# Qwiic_GPS-RTK2_-_ublox_ZED-F9P.net
KiCad netlist of a schematic drawn in EAGLE
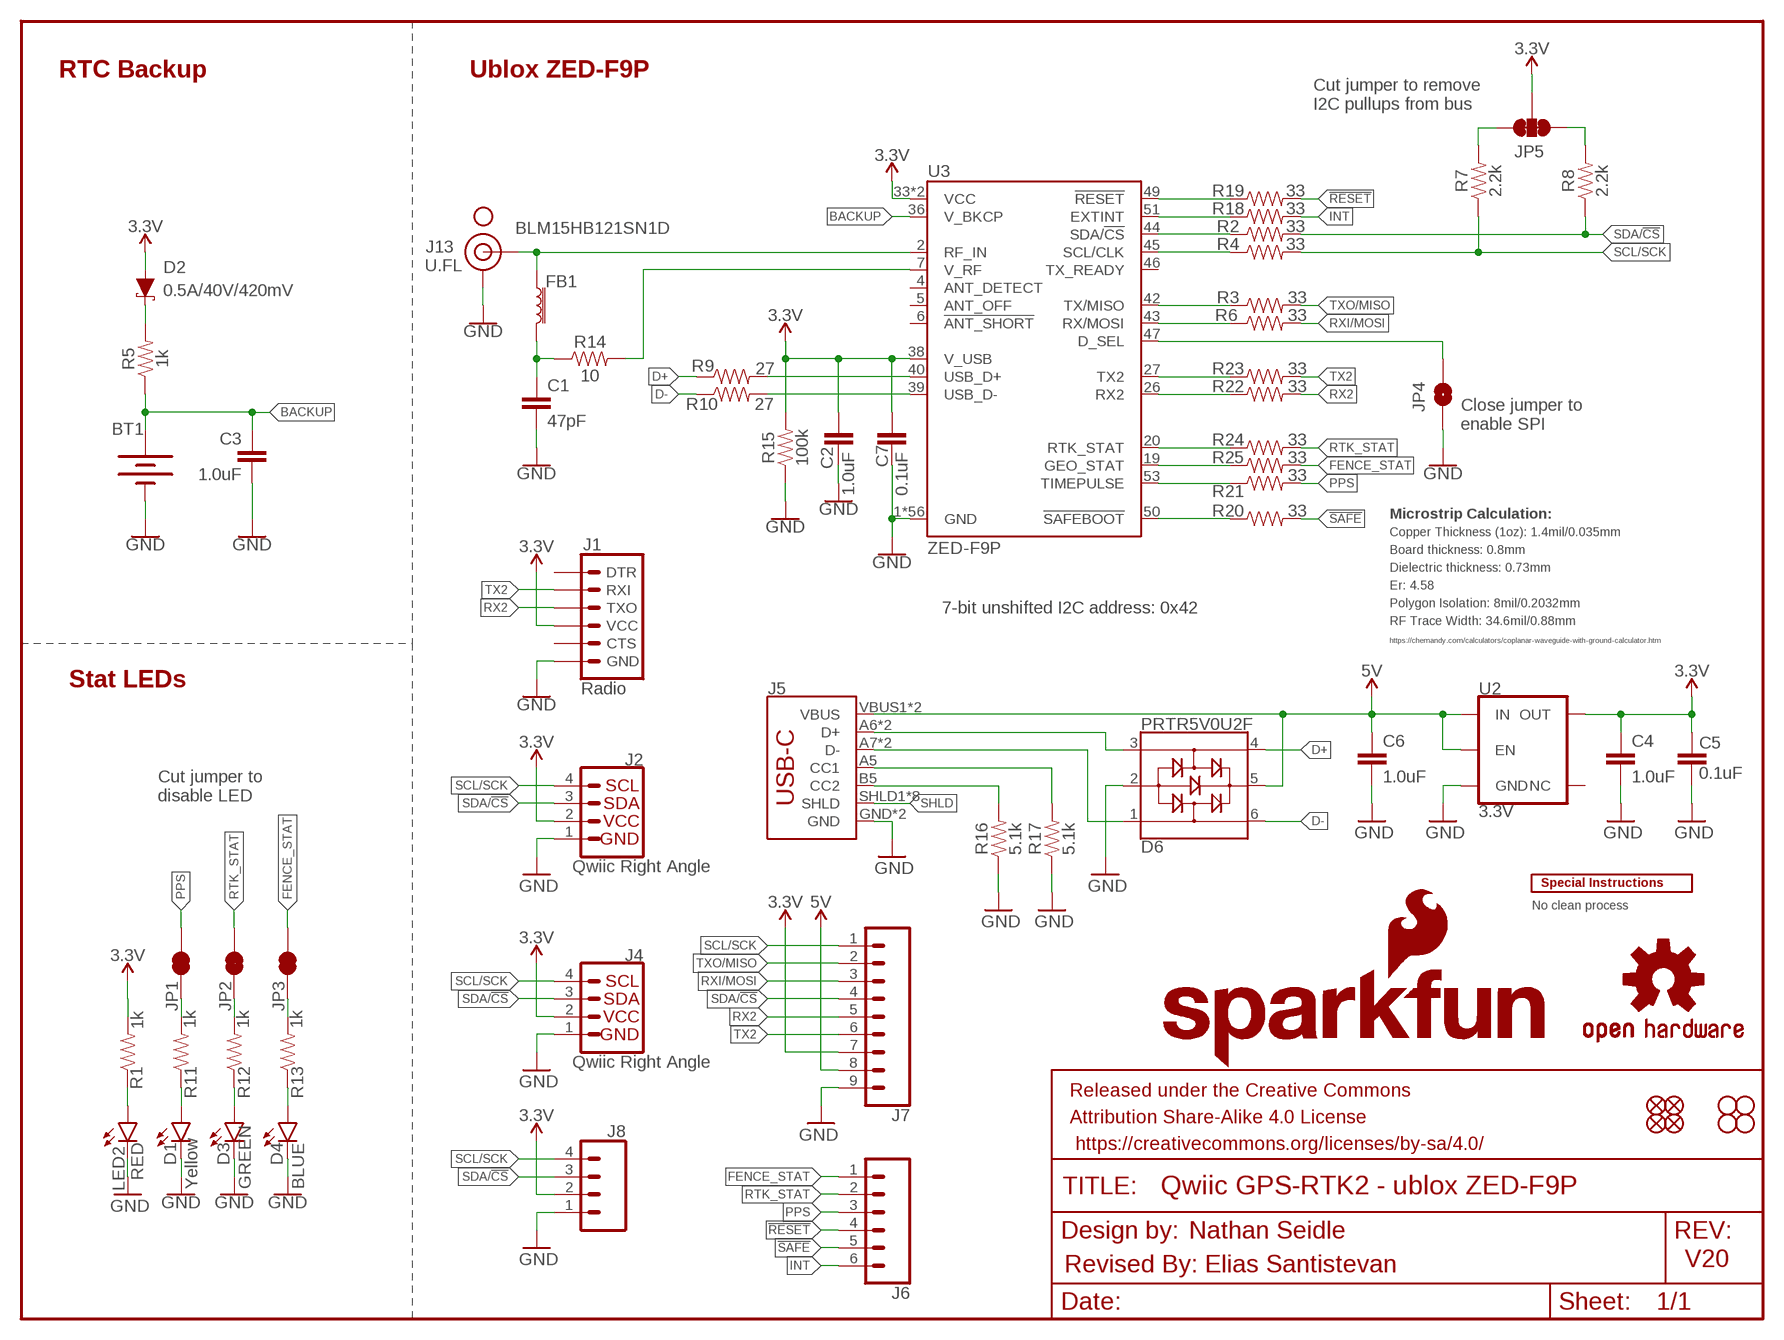
[diagram p0: schematic, sheet 1]

(export (version "E")
  (design (tool "Eeschema 10.0.6"))
  (components
    (comp (ref "BT1")
      (value "ML414H_IV01E_BATTERY")
      (footprint "eagle-import:ML414H_IV01E")
      (libsource (lib "eagle-import") (part "ML414H_IV01E_BATTERY"))
    )
    (comp (ref "C1")
      (value "47pF")
      (footprint "eagle-import:0603")
      (libsource (lib "eagle-import") (part "47PF-0603-50V-5%"))
    )
    (comp (ref "C2")
      (value "1.0uF")
      (footprint "eagle-import:0603")
      (libsource (lib "eagle-import") (part "1.0UF-0603-16V-10%"))
    )
    (comp (ref "C3")
      (value "1.0uF")
      (footprint "eagle-import:0603")
      (libsource (lib "eagle-import") (part "1.0UF-0603-16V-10%"))
    )
    (comp (ref "C4")
      (value "1.0uF")
      (footprint "eagle-import:0603")
      (libsource (lib "eagle-import") (part "1.0UF-0603-16V-10%"))
    )
    (comp (ref "C5")
      (value "0.1uF")
      (footprint "eagle-import:0603")
      (libsource (lib "eagle-import") (part "0.1UF-0603-25V-(+80/-20%)"))
    )
    (comp (ref "C6")
      (value "1.0uF")
      (footprint "eagle-import:0603")
      (libsource (lib "eagle-import") (part "1.0UF-0603-16V-10%"))
    )
    (comp (ref "C7")
      (value "0.1uF")
      (footprint "eagle-import:0603")
      (libsource (lib "eagle-import") (part "0.1UF-0603-25V-(+80/-20%)"))
    )
    (comp (ref "D1")
      (value "Yellow")
      (footprint "eagle-import:LED-0603")
      (libsource (lib "eagle-import") (part "LED-YELLOW0603"))
    )
    (comp (ref "D2")
      (value "0.5A/40V/420mV")
      (footprint "eagle-import:SOD-323")
      (libsource (lib "eagle-import") (part "DIODE-SCHOTTKY-PMEG4005EJ"))
    )
    (comp (ref "D3")
      (value "GREEN")
      (footprint "eagle-import:LED-0603")
      (libsource (lib "eagle-import") (part "LED-GREEN0603"))
    )
    (comp (ref "D4")
      (value "BLUE")
      (footprint "eagle-import:LED-0603")
      (libsource (lib "eagle-import") (part "LED-BLUE0603"))
    )
    (comp (ref "D6")
      (value "PRTR5V0U2F")
      (footprint "eagle-import:SOT886")
      (libsource (lib "eagle-import") (part "PRTR5V0U2F"))
    )
    (comp (ref "FB1")
      (value "FERRITE_BEAD-120_OHM-0402")
      (footprint "eagle-import:0402")
      (fields (field (name "MFG_PART") "BLM15HB121SN1D"))
      (libsource (lib "eagle-import") (part "FERRITE_BEAD-120_OHM-0402"))
    )
    (comp (ref "FRAME1")
      (value "FRAME-LETTER")
      (footprint "eagle-import:CREATIVE_COMMONS")
      (libsource (lib "eagle-import") (part "FRAME-LETTER"))
    )
    (comp (ref "J1")
      (value "Radio")
      (footprint "eagle-import:1X06_NO_SILK")
      (libsource (lib "eagle-import") (part "6_PIN_SERIAL_TARGET_NO_SILK"))
    )
    (comp (ref "J2")
      (value "Qwiic Right Angle")
      (footprint "eagle-import:JST04_1MM_RA")
      (libsource (lib "eagle-import") (part "I2C_STANDARDQWIIC"))
    )
    (comp (ref "J4")
      (value "Qwiic Right Angle")
      (footprint "eagle-import:JST04_1MM_RA")
      (libsource (lib "eagle-import") (part "I2C_STANDARDQWIIC"))
    )
    (comp (ref "J5")
      (value "USB_C2-LAYER")
      (footprint "eagle-import:USB-C-16P")
      (libsource (lib "eagle-import") (part "USB_C2-LAYER"))
    )
    (comp (ref "J6")
      (value "CONN_06NO_SILK_FEMALE_PTH")
      (footprint "eagle-import:1X06_NO_SILK")
      (libsource (lib "eagle-import") (part "CONN_06NO_SILK_FEMALE_PTH"))
    )
    (comp (ref "J7")
      (value "CONN_09NO_SILK")
      (footprint "eagle-import:1X09_NO_SILK")
      (libsource (lib "eagle-import") (part "CONN_09NO_SILK"))
    )
    (comp (ref "J8")
      (value "CONN_041X04_NO_SILK")
      (footprint "eagle-import:1X04_NO_SILK")
      (libsource (lib "eagle-import") (part "CONN_041X04_NO_SILK"))
    )
    (comp (ref "J13")
      (value "U.FL")
      (footprint "eagle-import:U.FL")
      (libsource (lib "eagle-import") (part "U.FL2PIN"))
    )
    (comp (ref "JP1")
      (value "JUMPER-SMT_2_NC_TRACE_SILK")
      (footprint "eagle-import:SMT-JUMPER_2_NC_TRACE_SILK")
      (libsource (lib "eagle-import") (part "JUMPER-SMT_2_NC_TRACE_SILK"))
    )
    (comp (ref "JP2")
      (value "JUMPER-SMT_2_NC_TRACE_SILK")
      (footprint "eagle-import:SMT-JUMPER_2_NC_TRACE_SILK")
      (libsource (lib "eagle-import") (part "JUMPER-SMT_2_NC_TRACE_SILK"))
    )
    (comp (ref "JP3")
      (value "JUMPER-SMT_2_NC_TRACE_SILK")
      (footprint "eagle-import:SMT-JUMPER_2_NC_TRACE_SILK")
      (libsource (lib "eagle-import") (part "JUMPER-SMT_2_NC_TRACE_SILK"))
    )
    (comp (ref "JP4")
      (value "JUMPER-SMT_2_NO_SILK")
      (footprint "eagle-import:SMT-JUMPER_2_NO_SILK")
      (libsource (lib "eagle-import") (part "JUMPER-SMT_2_NO_SILK"))
    )
    (comp (ref "JP5")
      (value "JUMPER-SMT_3_2-NC_TRACE_SILK")
      (footprint "eagle-import:SMT-JUMPER_3_2-NC_TRACE_SILK")
      (libsource (lib "eagle-import") (part "JUMPER-SMT_3_2-NC_TRACE_SILK"))
    )
    (comp (ref "JP21")
      (value "FIDUCIALUFIDUCIAL")
      (footprint "eagle-import:FIDUCIAL-MICRO")
      (libsource (lib "eagle-import") (part "FIDUCIALUFIDUCIAL"))
    )
    (comp (ref "JP31")
      (value "STAND-OFFTIGHT")
      (footprint "eagle-import:STAND-OFF-TIGHT")
      (libsource (lib "eagle-import") (part "STAND-OFFTIGHT"))
    )
    (comp (ref "JP41")
      (value "STAND-OFFTIGHT")
      (footprint "eagle-import:STAND-OFF-TIGHT")
      (libsource (lib "eagle-import") (part "STAND-OFFTIGHT"))
    )
    (comp (ref "JP61")
      (value "FIDUCIALUFIDUCIAL")
      (footprint "eagle-import:FIDUCIAL-MICRO")
      (libsource (lib "eagle-import") (part "FIDUCIALUFIDUCIAL"))
    )
    (comp (ref "JP71")
      (value "FIDUCIALUFIDUCIAL")
      (footprint "eagle-import:FIDUCIAL-MICRO")
      (libsource (lib "eagle-import") (part "FIDUCIALUFIDUCIAL"))
    )
    (comp (ref "JP81")
      (value "FIDUCIALUFIDUCIAL")
      (footprint "eagle-import:FIDUCIAL-MICRO")
      (libsource (lib "eagle-import") (part "FIDUCIALUFIDUCIAL"))
    )
    (comp (ref "JP91")
      (value "STAND-OFFTIGHT")
      (footprint "eagle-import:STAND-OFF-TIGHT")
      (libsource (lib "eagle-import") (part "STAND-OFFTIGHT"))
    )
    (comp (ref "JP101")
      (value "STAND-OFFTIGHT")
      (footprint "eagle-import:STAND-OFF-TIGHT")
      (libsource (lib "eagle-import") (part "STAND-OFFTIGHT"))
    )
    (comp (ref "LED2")
      (value "RED")
      (footprint "eagle-import:LED-0603")
      (libsource (lib "eagle-import") (part "LED-RED0603"))
    )
    (comp (ref "LOGO1")
      (value "OSHW-LOGOMINI")
      (footprint "eagle-import:OSHW-LOGO-MINI")
      (libsource (lib "eagle-import") (part "OSHW-LOGOMINI"))
    )
    (comp (ref "LOGO2")
      (value "SFE_LOGO_NAME_FLAME.1_INCH")
      (footprint "eagle-import:SFE_LOGO_NAME_FLAME_.1")
      (libsource (lib "eagle-import") (part "SFE_LOGO_NAME_FLAME.1_INCH"))
    )
    (comp (ref "R1")
      (value "1k")
      (footprint "eagle-import:0603")
      (libsource (lib "eagle-import") (part "1KOHM-0603-1/10W-1%"))
    )
    (comp (ref "R2")
      (value "33")
      (footprint "eagle-import:0603")
      (libsource (lib "eagle-import") (part "33OHM-0603-1/10W-1%"))
    )
    (comp (ref "R3")
      (value "33")
      (footprint "eagle-import:0603")
      (libsource (lib "eagle-import") (part "33OHM-0603-1/10W-1%"))
    )
    (comp (ref "R4")
      (value "33")
      (footprint "eagle-import:0603")
      (libsource (lib "eagle-import") (part "33OHM-0603-1/10W-1%"))
    )
    (comp (ref "R5")
      (value "1k")
      (footprint "eagle-import:0603")
      (libsource (lib "eagle-import") (part "1KOHM-0603-1/10W-1%"))
    )
    (comp (ref "R6")
      (value "33")
      (footprint "eagle-import:0603")
      (libsource (lib "eagle-import") (part "33OHM-0603-1/10W-1%"))
    )
    (comp (ref "R7")
      (value "2.2k")
      (footprint "eagle-import:0603")
      (libsource (lib "eagle-import") (part "2.2KOHM-0603-1/10W-1%"))
    )
    (comp (ref "R8")
      (value "2.2k")
      (footprint "eagle-import:0603")
      (libsource (lib "eagle-import") (part "2.2KOHM-0603-1/10W-1%"))
    )
    (comp (ref "R9")
      (value "27")
      (footprint "eagle-import:0603")
      (libsource (lib "eagle-import") (part "27OHM-0603-1/10W-1%"))
    )
    (comp (ref "R10")
      (value "27")
      (footprint "eagle-import:0603")
      (libsource (lib "eagle-import") (part "27OHM-0603-1/10W-1%"))
    )
    (comp (ref "R11")
      (value "1k")
      (footprint "eagle-import:0603")
      (libsource (lib "eagle-import") (part "1KOHM-0603-1/10W-1%"))
    )
    (comp (ref "R12")
      (value "1k")
      (footprint "eagle-import:0603")
      (libsource (lib "eagle-import") (part "1KOHM-0603-1/10W-1%"))
    )
    (comp (ref "R13")
      (value "1k")
      (footprint "eagle-import:0603")
      (libsource (lib "eagle-import") (part "1KOHM-0603-1/10W-1%"))
    )
    (comp (ref "R14")
      (value "10")
      (footprint "eagle-import:0603")
      (libsource (lib "eagle-import") (part "10OHM-0603-1/10W-1%"))
    )
    (comp (ref "R15")
      (value "100k")
      (footprint "eagle-import:0603")
      (libsource (lib "eagle-import") (part "100KOHM-0603-1/10W-1%"))
    )
    (comp (ref "R16")
      (value "5.1k")
      (footprint "eagle-import:0603")
      (libsource (lib "eagle-import") (part "5.1KOHM5.1KOHM-0603-1/10W-1%"))
    )
    (comp (ref "R17")
      (value "5.1k")
      (footprint "eagle-import:0603")
      (libsource (lib "eagle-import") (part "5.1KOHM5.1KOHM-0603-1/10W-1%"))
    )
    (comp (ref "R18")
      (value "33")
      (footprint "eagle-import:0603")
      (libsource (lib "eagle-import") (part "33OHM-0603-1/10W-1%"))
    )
    (comp (ref "R19")
      (value "33")
      (footprint "eagle-import:0603")
      (libsource (lib "eagle-import") (part "33OHM-0603-1/10W-1%"))
    )
    (comp (ref "R20")
      (value "33")
      (footprint "eagle-import:0603")
      (libsource (lib "eagle-import") (part "33OHM-0603-1/10W-1%"))
    )
    (comp (ref "R21")
      (value "33")
      (footprint "eagle-import:0603")
      (libsource (lib "eagle-import") (part "33OHM-0603-1/10W-1%"))
    )
    (comp (ref "R22")
      (value "33")
      (footprint "eagle-import:0603")
      (libsource (lib "eagle-import") (part "33OHM-0603-1/10W-1%"))
    )
    (comp (ref "R23")
      (value "33")
      (footprint "eagle-import:0603")
      (libsource (lib "eagle-import") (part "33OHM-0603-1/10W-1%"))
    )
    (comp (ref "R24")
      (value "33")
      (footprint "eagle-import:0603")
      (libsource (lib "eagle-import") (part "33OHM-0603-1/10W-1%"))
    )
    (comp (ref "R25")
      (value "33")
      (footprint "eagle-import:0603")
      (libsource (lib "eagle-import") (part "33OHM-0603-1/10W-1%"))
    )
    (comp (ref "U$2")
      (value "SPECIAL_INSTRUCTIONS-ORDERING")
      (footprint "eagle-import:ORDERING_INSTRUCTIONS")
      (libsource (lib "eagle-import") (part "SPECIAL_INSTRUCTIONS-ORDERING"))
    )
    (comp (ref "U$54")
      (value "SMA-ANTENNA-THREADED")
      (footprint "eagle-import:SMA-THREADED")
      (libsource (lib "eagle-import") (part "SMA-ANTENNA-THREADED"))
    )
    (comp (ref "U2")
      (value "3.3V")
      (footprint "eagle-import:SOT23-5")
      (libsource (lib "eagle-import") (part "V_REG_AP2112K-3.3V"))
    )
    (comp (ref "U3")
      (value "ZED-F9P")
      (footprint "eagle-import:ZED-F9P")
      (libsource (lib "eagle-import") (part "ZED-F9P"))
    )
  )
  (nets
    (net (code "1") (name "/SDA{slash}~{CS}") (class "Default")
      (node (ref "J2") (pin "3") (pinfunction "3_3") (pintype "passive"))
      (node (ref "J4") (pin "3") (pinfunction "3_3") (pintype "passive"))
      (node (ref "J7") (pin "4") (pinfunction "4_4") (pintype "passive"))
      (node (ref "J8") (pin "3") (pinfunction "3_3") (pintype "passive"))
      (node (ref "R2") (pin "2") (pinfunction "2_2") (pintype "passive"))
      (node (ref "R8") (pin "1") (pinfunction "1_1") (pintype "passive"))
    )
    (net (code "2") (name "/~{RESET}") (class "Default")
      (node (ref "J6") (pin "4") (pinfunction "4_4") (pintype "passive"))
      (node (ref "R19") (pin "2") (pinfunction "2_2") (pintype "passive"))
    )
    (net (code "3") (name "/~{SAFE}") (class "Default")
      (node (ref "J6") (pin "5") (pinfunction "5_5") (pintype "passive"))
      (node (ref "R20") (pin "2") (pinfunction "2_2") (pintype "passive"))
    )
    (net (code "4") (name "3.3V") (class "Default")
      (node (ref "C2") (pin "1") (pinfunction "1_1") (pintype "passive"))
      (node (ref "C4") (pin "1") (pinfunction "1_1") (pintype "passive"))
      (node (ref "C5") (pin "2") (pinfunction "2_2") (pintype "passive"))
      (node (ref "C7") (pin "2") (pinfunction "2_2") (pintype "passive"))
      (node (ref "D2") (pin "A") (pinfunction "A_A") (pintype "passive"))
      (node (ref "J1") (pin "4") (pinfunction "VCC_4") (pintype "passive"))
      (node (ref "J2") (pin "2") (pinfunction "2_2") (pintype "power_in"))
      (node (ref "J4") (pin "2") (pinfunction "2_2") (pintype "power_in"))
      (node (ref "J7") (pin "7") (pinfunction "7_7") (pintype "passive"))
      (node (ref "J8") (pin "2") (pinfunction "2_2") (pintype "passive"))
      (node (ref "JP5") (pin "2") (pinfunction "2_2") (pintype "passive"))
      (node (ref "R1") (pin "2") (pinfunction "2_2") (pintype "passive"))
      (node (ref "R15") (pin "2") (pinfunction "2_2") (pintype "passive"))
      (node (ref "U2") (pin "5") (pinfunction "OUT_5") (pintype "passive"))
      (node (ref "U3") (pin "33") (pinfunction "VCC_33") (pintype "bidirectional"))
      (node (ref "U3") (pin "34") (pinfunction "VCC_34") (pintype "bidirectional"))
      (node (ref "U3") (pin "38") (pinfunction "V_USB_38") (pintype "bidirectional"))
    )
    (net (code "5") (name "5V") (class "Default")
      (node (ref "C6") (pin "1") (pinfunction "1_1") (pintype "passive"))
      (node (ref "D6") (pin "5") (pinfunction "5_5") (pintype "bidirectional"))
      (node (ref "J5") (pin "VBUS1") (pinfunction "VBUS_VBUS1") (pintype "bidirectional"))
      (node (ref "J5") (pin "VBUS2") (pinfunction "VBUS_VBUS2") (pintype "bidirectional"))
      (node (ref "J7") (pin "8") (pinfunction "8_8") (pintype "passive"))
      (node (ref "U2") (pin "1") (pinfunction "IN_1") (pintype "input"))
      (node (ref "U2") (pin "3") (pinfunction "EN_3") (pintype "input"))
    )
    (net (code "6") (name "BACKUP") (class "Default")
      (node (ref "BT1") (pin "+") (pinfunction "+_+") (pintype "power_in"))
      (node (ref "C3") (pin "1") (pinfunction "1_1") (pintype "passive"))
      (node (ref "R5") (pin "1") (pinfunction "1_1") (pintype "passive"))
      (node (ref "U3") (pin "36") (pinfunction "V_BKCP_36") (pintype "bidirectional"))
    )
    (net (code "7") (name "D+") (class "Default")
      (node (ref "D6") (pin "4") (pinfunction "4_4") (pintype "bidirectional"))
      (node (ref "R9") (pin "1") (pinfunction "1_1") (pintype "passive"))
    )
    (net (code "8") (name "D-") (class "Default")
      (node (ref "D6") (pin "6") (pinfunction "6_6") (pintype "bidirectional"))
      (node (ref "R10") (pin "1") (pinfunction "1_1") (pintype "passive"))
    )
    (net (code "9") (name "FENCE_STAT") (class "Default")
      (node (ref "J6") (pin "1") (pinfunction "1_1") (pintype "passive"))
      (node (ref "JP3") (pin "2") (pinfunction "2_2") (pintype "passive"))
      (node (ref "R25") (pin "2") (pinfunction "2_2") (pintype "passive"))
    )
    (net (code "10") (name "GND") (class "Default")
      (node (ref "BT1") (pin "-") (pinfunction "-_-") (pintype "power_in"))
      (node (ref "C1") (pin "2") (pinfunction "2_2") (pintype "passive"))
      (node (ref "C2") (pin "2") (pinfunction "2_2") (pintype "passive"))
      (node (ref "C3") (pin "2") (pinfunction "2_2") (pintype "passive"))
      (node (ref "C4") (pin "2") (pinfunction "2_2") (pintype "passive"))
      (node (ref "C5") (pin "1") (pinfunction "1_1") (pintype "passive"))
      (node (ref "C6") (pin "2") (pinfunction "2_2") (pintype "passive"))
      (node (ref "C7") (pin "1") (pinfunction "1_1") (pintype "passive"))
      (node (ref "D1") (pin "C") (pinfunction "C_C") (pintype "passive"))
      (node (ref "D3") (pin "C") (pinfunction "C_C") (pintype "passive"))
      (node (ref "D4") (pin "C") (pinfunction "C_C") (pintype "passive"))
      (node (ref "D6") (pin "2") (pinfunction "2_2") (pintype "bidirectional"))
      (node (ref "J1") (pin "6") (pinfunction "GND_6") (pintype "passive"))
      (node (ref "J13") (pin "1") (pinfunction "GND_1") (pintype "bidirectional"))
      (node (ref "J13") (pin "2") (pinfunction "GND_2") (pintype "bidirectional"))
      (node (ref "J2") (pin "1") (pinfunction "1_1") (pintype "power_in"))
      (node (ref "J4") (pin "1") (pinfunction "1_1") (pintype "power_in"))
      (node (ref "J5") (pin "GND") (pinfunction "GND_GND") (pintype "bidirectional"))
      (node (ref "J5") (pin "GND2") (pinfunction "GND_GND2") (pintype "bidirectional"))
      (node (ref "J7") (pin "9") (pinfunction "9_9") (pintype "passive"))
      (node (ref "J8") (pin "1") (pinfunction "1_1") (pintype "passive"))
      (node (ref "JP4") (pin "1") (pinfunction "1_1") (pintype "passive"))
      (node (ref "LED2") (pin "C") (pinfunction "C_C") (pintype "passive"))
      (node (ref "R15") (pin "1") (pinfunction "1_1") (pintype "passive"))
      (node (ref "R16") (pin "1") (pinfunction "1_1") (pintype "passive"))
      (node (ref "R17") (pin "1") (pinfunction "1_1") (pintype "passive"))
      (node (ref "U2") (pin "2") (pinfunction "GND_2") (pintype "input"))
      (node (ref "U3") (pin "1") (pinfunction "GND_1") (pintype "bidirectional"))
      (node (ref "U3") (pin "100") (pinfunction "GND_100") (pintype "bidirectional"))
      (node (ref "U3") (pin "101") (pinfunction "GND_101") (pintype "bidirectional"))
      (node (ref "U3") (pin "102") (pinfunction "GND_102") (pintype "bidirectional"))
      (node (ref "U3") (pin "12") (pinfunction "GND_12") (pintype "bidirectional"))
      (node (ref "U3") (pin "14") (pinfunction "GND_14") (pintype "bidirectional"))
      (node (ref "U3") (pin "3") (pinfunction "GND_3") (pintype "bidirectional"))
      (node (ref "U3") (pin "32") (pinfunction "GND_32") (pintype "bidirectional"))
      (node (ref "U3") (pin "37") (pinfunction "GND_37") (pintype "bidirectional"))
      (node (ref "U3") (pin "41") (pinfunction "GND_41") (pintype "bidirectional"))
      (node (ref "U3") (pin "48") (pinfunction "GND_48") (pintype "bidirectional"))
      (node (ref "U3") (pin "55") (pinfunction "GND_55") (pintype "bidirectional"))
      (node (ref "U3") (pin "56") (pinfunction "GND_56") (pintype "bidirectional"))
      (node (ref "U3") (pin "57") (pinfunction "GND_57") (pintype "bidirectional"))
      (node (ref "U3") (pin "58") (pinfunction "GND_58") (pintype "bidirectional"))
      (node (ref "U3") (pin "59") (pinfunction "GND_59") (pintype "bidirectional"))
      (node (ref "U3") (pin "60") (pinfunction "GND_60") (pintype "bidirectional"))
      (node (ref "U3") (pin "61") (pinfunction "GND_61") (pintype "bidirectional"))
      (node (ref "U3") (pin "62") (pinfunction "GND_62") (pintype "bidirectional"))
      (node (ref "U3") (pin "63") (pinfunction "GND_63") (pintype "bidirectional"))
      (node (ref "U3") (pin "64") (pinfunction "GND_64") (pintype "bidirectional"))
      (node (ref "U3") (pin "65") (pinfunction "GND_65") (pintype "bidirectional"))
      (node (ref "U3") (pin "66") (pinfunction "GND_66") (pintype "bidirectional"))
      (node (ref "U3") (pin "67") (pinfunction "GND_67") (pintype "bidirectional"))
      (node (ref "U3") (pin "68") (pinfunction "GND_68") (pintype "bidirectional"))
      (node (ref "U3") (pin "69") (pinfunction "GND_69") (pintype "bidirectional"))
      (node (ref "U3") (pin "70") (pinfunction "GND_70") (pintype "bidirectional"))
      (node (ref "U3") (pin "71") (pinfunction "GND_71") (pintype "bidirectional"))
      (node (ref "U3") (pin "72") (pinfunction "GND_72") (pintype "bidirectional"))
      (node (ref "U3") (pin "73") (pinfunction "GND_73") (pintype "bidirectional"))
      (node (ref "U3") (pin "74") (pinfunction "GND_74") (pintype "bidirectional"))
      (node (ref "U3") (pin "75") (pinfunction "GND_75") (pintype "bidirectional"))
      (node (ref "U3") (pin "76") (pinfunction "GND_76") (pintype "bidirectional"))
      (node (ref "U3") (pin "77") (pinfunction "GND_77") (pintype "bidirectional"))
      (node (ref "U3") (pin "78") (pinfunction "GND_78") (pintype "bidirectional"))
      (node (ref "U3") (pin "79") (pinfunction "GND_79") (pintype "bidirectional"))
      (node (ref "U3") (pin "80") (pinfunction "GND_80") (pintype "bidirectional"))
      (node (ref "U3") (pin "81") (pinfunction "GND_81") (pintype "bidirectional"))
      (node (ref "U3") (pin "82") (pinfunction "GND_82") (pintype "bidirectional"))
      (node (ref "U3") (pin "83") (pinfunction "GND_83") (pintype "bidirectional"))
      (node (ref "U3") (pin "84") (pinfunction "GND_84") (pintype "bidirectional"))
      (node (ref "U3") (pin "85") (pinfunction "GND_85") (pintype "bidirectional"))
      (node (ref "U3") (pin "86") (pinfunction "GND_86") (pintype "bidirectional"))
      (node (ref "U3") (pin "87") (pinfunction "GND_87") (pintype "bidirectional"))
      (node (ref "U3") (pin "88") (pinfunction "GND_88") (pintype "bidirectional"))
      (node (ref "U3") (pin "89") (pinfunction "GND_89") (pintype "bidirectional"))
      (node (ref "U3") (pin "90") (pinfunction "GND_90") (pintype "bidirectional"))
      (node (ref "U3") (pin "91") (pinfunction "GND_91") (pintype "bidirectional"))
      (node (ref "U3") (pin "92") (pinfunction "GND_92") (pintype "bidirectional"))
      (node (ref "U3") (pin "93") (pinfunction "GND_93") (pintype "bidirectional"))
      (node (ref "U3") (pin "94") (pinfunction "GND_94") (pintype "bidirectional"))
      (node (ref "U3") (pin "95") (pinfunction "GND_95") (pintype "bidirectional"))
      (node (ref "U3") (pin "96") (pinfunction "GND_96") (pintype "bidirectional"))
      (node (ref "U3") (pin "97") (pinfunction "GND_97") (pintype "bidirectional"))
      (node (ref "U3") (pin "98") (pinfunction "GND_98") (pintype "bidirectional"))
      (node (ref "U3") (pin "99") (pinfunction "GND_99") (pintype "bidirectional"))
    )
    (net (code "11") (name "INT") (class "Default")
      (node (ref "J6") (pin "6") (pinfunction "6_6") (pintype "passive"))
      (node (ref "R18") (pin "2") (pinfunction "2_2") (pintype "passive"))
    )
    (net (code "12") (name "Net-(C1-Pad1)") (class "Default")
      (node (ref "C1") (pin "1") (pinfunction "1_1") (pintype "passive"))
      (node (ref "FB1") (pin "2") (pinfunction "2_2") (pintype "passive"))
      (node (ref "R14") (pin "1") (pinfunction "1_1") (pintype "passive"))
    )
    (net (code "13") (name "Net-(D1-PadA)") (class "Default")
      (node (ref "D1") (pin "A") (pinfunction "A_A") (pintype "passive"))
      (node (ref "R11") (pin "1") (pinfunction "1_1") (pintype "passive"))
    )
    (net (code "14") (name "Net-(D2-PadC)") (class "Default")
      (node (ref "D2") (pin "C") (pinfunction "C_C") (pintype "passive"))
      (node (ref "R5") (pin "2") (pinfunction "2_2") (pintype "passive"))
    )
    (net (code "15") (name "Net-(D3-PadA)") (class "Default")
      (node (ref "D3") (pin "A") (pinfunction "A_A") (pintype "passive"))
      (node (ref "R12") (pin "1") (pinfunction "1_1") (pintype "passive"))
    )
    (net (code "16") (name "Net-(D4-PadA)") (class "Default")
      (node (ref "D4") (pin "A") (pinfunction "A_A") (pintype "passive"))
      (node (ref "R13") (pin "1") (pinfunction "1_1") (pintype "passive"))
    )
    (net (code "17") (name "Net-(D6-Pad1)") (class "Default")
      (node (ref "D6") (pin "1") (pinfunction "1_1") (pintype "bidirectional"))
      (node (ref "J5") (pin "A7") (pinfunction "D-_A7") (pintype "bidirectional"))
      (node (ref "J5") (pin "B7") (pinfunction "D-_B7") (pintype "bidirectional"))
    )
    (net (code "18") (name "Net-(D6-Pad3)") (class "Default")
      (node (ref "D6") (pin "3") (pinfunction "3_3") (pintype "bidirectional"))
      (node (ref "J5") (pin "A6") (pinfunction "D+_A6") (pintype "bidirectional"))
      (node (ref "J5") (pin "B6") (pinfunction "D+_B6") (pintype "bidirectional"))
    )
    (net (code "19") (name "Net-(J5-CC1)") (class "Default")
      (node (ref "J5") (pin "A5") (pinfunction "CC1_A5") (pintype "bidirectional"))
      (node (ref "R17") (pin "2") (pinfunction "2_2") (pintype "passive"))
    )
    (net (code "20") (name "Net-(J5-CC2)") (class "Default")
      (node (ref "J5") (pin "B5") (pinfunction "CC2_B5") (pintype "bidirectional"))
      (node (ref "R16") (pin "2") (pinfunction "2_2") (pintype "passive"))
    )
    (net (code "21") (name "Net-(J13-SIGNAL)") (class "Default")
      (node (ref "FB1") (pin "1") (pinfunction "1_1") (pintype "passive"))
      (node (ref "J13") (pin "FEED") (pinfunction "SIGNAL_FEED") (pintype "bidirectional"))
      (node (ref "U3") (pin "2") (pinfunction "RF_IN_2") (pintype "bidirectional"))
    )
    (net (code "22") (name "Net-(JP1-Pad1)") (class "Default")
      (node (ref "JP1") (pin "1") (pinfunction "1_1") (pintype "passive"))
      (node (ref "R11") (pin "2") (pinfunction "2_2") (pintype "passive"))
    )
    (net (code "23") (name "Net-(JP2-Pad1)") (class "Default")
      (node (ref "JP2") (pin "1") (pinfunction "1_1") (pintype "passive"))
      (node (ref "R12") (pin "2") (pinfunction "2_2") (pintype "passive"))
    )
    (net (code "24") (name "Net-(JP3-Pad1)") (class "Default")
      (node (ref "JP3") (pin "1") (pinfunction "1_1") (pintype "passive"))
      (node (ref "R13") (pin "2") (pinfunction "2_2") (pintype "passive"))
    )
    (net (code "25") (name "Net-(JP5-Pad1)") (class "Default")
      (node (ref "JP5") (pin "1") (pinfunction "1_1") (pintype "passive"))
      (node (ref "R8") (pin "2") (pinfunction "2_2") (pintype "passive"))
    )
    (net (code "26") (name "Net-(JP5-Pad3)") (class "Default")
      (node (ref "JP5") (pin "3") (pinfunction "3_3") (pintype "passive"))
      (node (ref "R7") (pin "2") (pinfunction "2_2") (pintype "passive"))
    )
    (net (code "27") (name "Net-(LED2-PadA)") (class "Default")
      (node (ref "LED2") (pin "A") (pinfunction "A_A") (pintype "passive"))
      (node (ref "R1") (pin "1") (pinfunction "1_1") (pintype "passive"))
    )
    (net (code "28") (name "Net-(U3-D_SEL)") (class "Default")
      (node (ref "JP4") (pin "2") (pinfunction "2_2") (pintype "passive"))
      (node (ref "U3") (pin "47") (pinfunction "D_SEL_47") (pintype "bidirectional"))
    )
    (net (code "29") (name "Net-(U3-EXTINT)") (class "Default")
      (node (ref "R18") (pin "1") (pinfunction "1_1") (pintype "passive"))
      (node (ref "U3") (pin "51") (pinfunction "EXTINT_51") (pintype "bidirectional"))
    )
    (net (code "30") (name "Net-(U3-GEO_STAT)") (class "Default")
      (node (ref "R25") (pin "1") (pinfunction "1_1") (pintype "passive"))
      (node (ref "U3") (pin "19") (pinfunction "GEO_STAT_19") (pintype "bidirectional"))
    )
    (net (code "31") (name "Net-(U3-RTK_STAT)") (class "Default")
      (node (ref "R24") (pin "1") (pinfunction "1_1") (pintype "passive"))
      (node (ref "U3") (pin "20") (pinfunction "RTK_STAT_20") (pintype "bidirectional"))
    )
    (net (code "32") (name "Net-(U3-RX2)") (class "Default")
      (node (ref "R22") (pin "1") (pinfunction "1_1") (pintype "passive"))
      (node (ref "U3") (pin "26") (pinfunction "RX2_26") (pintype "bidirectional"))
    )
    (net (code "33") (name "Net-(U3-RX{slash}MOSI)") (class "Default")
      (node (ref "R6") (pin "1") (pinfunction "1_1") (pintype "passive"))
      (node (ref "U3") (pin "43") (pinfunction "RX/MOSI_43") (pintype "bidirectional"))
    )
    (net (code "34") (name "Net-(U3-SCL{slash}CLK)") (class "Default")
      (node (ref "R4") (pin "1") (pinfunction "1_1") (pintype "passive"))
      (node (ref "U3") (pin "45") (pinfunction "SCL/CLK_45") (pintype "bidirectional"))
    )
    (net (code "35") (name "Net-(U3-SDA{slash}~{CS})") (class "Default")
      (node (ref "R2") (pin "1") (pinfunction "1_1") (pintype "passive"))
      (node (ref "U3") (pin "44") (pinfunction "SDA/~{CS}_44") (pintype "bidirectional"))
    )
    (net (code "36") (name "Net-(U3-TIMEPULSE)") (class "Default")
      (node (ref "R21") (pin "1") (pinfunction "1_1") (pintype "passive"))
      (node (ref "U3") (pin "53") (pinfunction "TIMEPULSE_53") (pintype "bidirectional"))
    )
    (net (code "37") (name "Net-(U3-TX2)") (class "Default")
      (node (ref "R23") (pin "1") (pinfunction "1_1") (pintype "passive"))
      (node (ref "U3") (pin "27") (pinfunction "TX2_27") (pintype "bidirectional"))
    )
    (net (code "38") (name "Net-(U3-TX{slash}MISO)") (class "Default")
      (node (ref "R3") (pin "1") (pinfunction "1_1") (pintype "passive"))
      (node (ref "U3") (pin "42") (pinfunction "TX/MISO_42") (pintype "bidirectional"))
    )
    (net (code "39") (name "Net-(U3-USB_D+)") (class "Default")
      (node (ref "R9") (pin "2") (pinfunction "2_2") (pintype "passive"))
      (node (ref "U3") (pin "40") (pinfunction "USB_D+_40") (pintype "bidirectional"))
    )
    (net (code "40") (name "Net-(U3-USB_D-)") (class "Default")
      (node (ref "R10") (pin "2") (pinfunction "2_2") (pintype "passive"))
      (node (ref "U3") (pin "39") (pinfunction "USB_D-_39") (pintype "bidirectional"))
    )
    (net (code "41") (name "Net-(U3-V_RF)") (class "Default")
      (node (ref "R14") (pin "2") (pinfunction "2_2") (pintype "passive"))
      (node (ref "U3") (pin "7") (pinfunction "V_RF_7") (pintype "bidirectional"))
    )
    (net (code "42") (name "Net-(U3-~{RESET})") (class "Default")
      (node (ref "R19") (pin "1") (pinfunction "1_1") (pintype "passive"))
      (node (ref "U3") (pin "49") (pinfunction "~{RESET}_49") (pintype "bidirectional"))
    )
    (net (code "43") (name "Net-(U3-~{SAFEBOOT})") (class "Default")
      (node (ref "R20") (pin "1") (pinfunction "1_1") (pintype "passive"))
      (node (ref "U3") (pin "50") (pinfunction "~{SAFEBOOT}_50") (pintype "bidirectional"))
    )
    (net (code "44") (name "PPS") (class "Default")
      (node (ref "J6") (pin "3") (pinfunction "3_3") (pintype "passive"))
      (node (ref "JP1") (pin "2") (pinfunction "2_2") (pintype "passive"))
      (node (ref "R21") (pin "2") (pinfunction "2_2") (pintype "passive"))
    )
    (net (code "45") (name "RTK_STAT") (class "Default")
      (node (ref "J6") (pin "2") (pinfunction "2_2") (pintype "passive"))
      (node (ref "JP2") (pin "2") (pinfunction "2_2") (pintype "passive"))
      (node (ref "R24") (pin "2") (pinfunction "2_2") (pintype "passive"))
    )
    (net (code "46") (name "RX2") (class "Default")
      (node (ref "J1") (pin "3") (pinfunction "TXO_3") (pintype "passive"))
      (node (ref "J7") (pin "5") (pinfunction "5_5") (pintype "passive"))
      (node (ref "R22") (pin "2") (pinfunction "2_2") (pintype "passive"))
    )
    (net (code "47") (name "RXI{slash}MOSI") (class "Default")
      (node (ref "J7") (pin "3") (pinfunction "3_3") (pintype "passive"))
      (node (ref "R6") (pin "2") (pinfunction "2_2") (pintype "passive"))
    )
    (net (code "48") (name "SCL{slash}SCK") (class "Default")
      (node (ref "J2") (pin "4") (pinfunction "4_4") (pintype "passive"))
      (node (ref "J4") (pin "4") (pinfunction "4_4") (pintype "passive"))
      (node (ref "J7") (pin "1") (pinfunction "1_1") (pintype "passive"))
      (node (ref "J8") (pin "4") (pinfunction "4_4") (pintype "passive"))
      (node (ref "R4") (pin "2") (pinfunction "2_2") (pintype "passive"))
      (node (ref "R7") (pin "1") (pinfunction "1_1") (pintype "passive"))
    )
    (net (code "49") (name "SHLD") (class "Default")
      (node (ref "J5") (pin "SHLD1") (pinfunction "SHLD_SHLD1") (pintype "bidirectional"))
      (node (ref "J5") (pin "SHLD2") (pinfunction "SHLD_SHLD2") (pintype "bidirectional"))
      (node (ref "J5") (pin "SHLD3") (pinfunction "SHLD_SHLD3") (pintype "bidirectional"))
      (node (ref "J5") (pin "SHLD4") (pinfunction "SHLD_SHLD4") (pintype "bidirectional"))
      (node (ref "J5") (pin "SHLD5") (pinfunction "SHLD_SHLD5") (pintype "bidirectional"))
      (node (ref "J5") (pin "SHLD6") (pinfunction "SHLD_SHLD6") (pintype "bidirectional"))
      (node (ref "J5") (pin "SHLD7") (pinfunction "SHLD_SHLD7") (pintype "bidirectional"))
      (node (ref "J5") (pin "SHLD8") (pinfunction "SHLD_SHLD8") (pintype "bidirectional"))
    )
    (net (code "50") (name "TX2") (class "Default")
      (node (ref "J1") (pin "2") (pinfunction "RXI_2") (pintype "passive"))
      (node (ref "J7") (pin "6") (pinfunction "6_6") (pintype "passive"))
      (node (ref "R23") (pin "2") (pinfunction "2_2") (pintype "passive"))
    )
    (net (code "51") (name "TXO{slash}MISO") (class "Default")
      (node (ref "J7") (pin "2") (pinfunction "2_2") (pintype "passive"))
      (node (ref "R3") (pin "2") (pinfunction "2_2") (pintype "passive"))
    )
    (net (code "52") (name "unconnected-(J1-CTS-Pad5)") (class "Default")
      (node (ref "J1") (pin "5") (pinfunction "CTS_5") (pintype "passive"))
    )
    (net (code "53") (name "unconnected-(J1-DTR-Pad1)") (class "Default")
      (node (ref "J1") (pin "1") (pinfunction "DTR_1") (pintype "passive"))
    )
    (net (code "54") (name "unconnected-(U2-NC-Pad4)") (class "Default")
      (node (ref "U2") (pin "4") (pinfunction "NC_4") (pintype "no_connect"))
    )
    (net (code "55") (name "unconnected-(U3-ANT_DETECT-Pad4)") (class "Default")
      (node (ref "U3") (pin "4") (pinfunction "ANT_DETECT_4") (pintype "bidirectional"))
    )
    (net (code "56") (name "unconnected-(U3-ANT_OFF-Pad5)") (class "Default")
      (node (ref "U3") (pin "5") (pinfunction "ANT_OFF_5") (pintype "bidirectional"))
    )
    (net (code "57") (name "unconnected-(U3-TX_READY-Pad46)") (class "Default")
      (node (ref "U3") (pin "46") (pinfunction "TX_READY_46") (pintype "bidirectional"))
    )
    (net (code "58") (name "unconnected-(U3-~{ANT_SHORT}-Pad6)") (class "Default")
      (node (ref "U3") (pin "6") (pinfunction "~{ANT_SHORT}_6") (pintype "bidirectional"))
    )
  )
)
